# didah.net
KiCad netlist of a schematic drawn in EAGLE
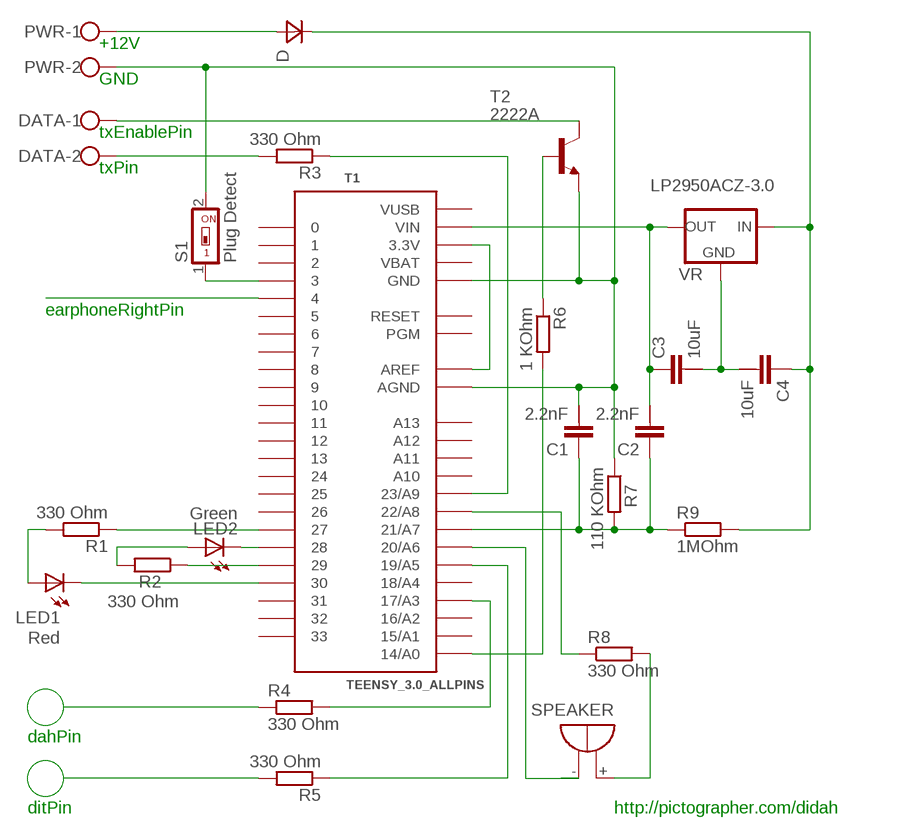
[diagram p0: schematic, sheet 1]

(export (version "E")
  (design (tool "Eeschema 10.0.6"))
  (components
    (comp (ref "C1")
      (value "2.2nF")
      (footprint "eagle-import:C2.5_5-6")
      (libsource (lib "eagle-import") (part "C-2.5-5/6"))
    )
    (comp (ref "C2")
      (value "2.2nF")
      (footprint "eagle-import:C2.5_5-6")
      (libsource (lib "eagle-import") (part "C-2.5-5/6"))
    )
    (comp (ref "C3")
      (value "10uF")
      (footprint "eagle-import:C2.5_5-6")
      (libsource (lib "eagle-import") (part "C-2.5-5/6"))
    )
    (comp (ref "C4")
      (value "10uF")
      (footprint "eagle-import:C2.5_5-6")
      (libsource (lib "eagle-import") (part "C-2.5-5/6"))
    )
    (comp (ref "D")
      (value "DIODE")
      (footprint "eagle-import:DIODE")
      (libsource (lib "eagle-import") (part "DIODE"))
    )
    (comp (ref "DATA")
      (value "W237-102")
      (footprint "eagle-import:W237-102")
      (fields (field (name "MPN") "237-102"))
      (libsource (lib "eagle-import") (part "W237-102"))
    )
    (comp (ref "LED1")
      (value "Red")
      (footprint "eagle-import:LED_SML0603")
      (libsource (lib "eagle-import") (part "LED_ESML0603"))
    )
    (comp (ref "LED2")
      (value "Green")
      (footprint "eagle-import:LED_SML0603")
      (libsource (lib "eagle-import") (part "LED_ESML0603"))
    )
    (comp (ref "PWR")
      (value "W237-102")
      (footprint "eagle-import:W237-102")
      (fields (field (name "MPN") "237-102"))
      (libsource (lib "eagle-import") (part "W237-102"))
    )
    (comp (ref "R1")
      (value "330 Ohm")
      (footprint "eagle-import:R0402")
      (libsource (lib "eagle-import") (part "RR0402"))
    )
    (comp (ref "R2")
      (value "330 Ohm")
      (footprint "eagle-import:R0402")
      (libsource (lib "eagle-import") (part "RR0402"))
    )
    (comp (ref "R3")
      (value "330 Ohm")
      (footprint "eagle-import:R0402")
      (libsource (lib "eagle-import") (part "RR0402"))
    )
    (comp (ref "R4")
      (value "330 Ohm")
      (footprint "eagle-import:R0402")
      (libsource (lib "eagle-import") (part "RR0402"))
    )
    (comp (ref "R5")
      (value "330 Ohm")
      (footprint "eagle-import:R0402")
      (libsource (lib "eagle-import") (part "RR0402"))
    )
    (comp (ref "R6")
      (value "1 KOhm")
      (footprint "eagle-import:R0402")
      (libsource (lib "eagle-import") (part "RR0402"))
    )
    (comp (ref "R7")
      (value "110 KOhm")
      (footprint "eagle-import:0204_7")
      (libsource (lib "eagle-import") (part "R0204/7"))
    )
    (comp (ref "R8")
      (value "330 Ohm")
      (footprint "eagle-import:R0402")
      (libsource (lib "eagle-import") (part "RR0402"))
    )
    (comp (ref "R9")
      (value "1MOhm")
      (footprint "eagle-import:0204_7")
      (libsource (lib "eagle-import") (part "R0204/7"))
    )
    (comp (ref "S1")
      (value "Plug Detect")
      (footprint "eagle-import:SMS-001")
      (libsource (lib "eagle-import") (part "SWS001"))
    )
    (comp (ref "SPEAKER")
      (value "BMT1205XH7.5")
      (footprint "eagle-import:BMT1205XH7.5")
      (libsource (lib "eagle-import") (part "BMT1205XH7.5"))
    )
    (comp (ref "T1")
      (value "TEENSY_3.0_ALLPINS")
      (footprint "eagle-import:TEENSY_3.0_ALLPINS")
      (libsource (lib "eagle-import") (part "TEENSY_3.0_ALLPINS"))
    )
    (comp (ref "T2")
      (value "2222A")
      (footprint "eagle-import:TO92-EBC")
      (libsource (lib "eagle-import") (part "-NPN-TO92-EBC2N2222"))
    )
    (comp (ref "VR")
      (value "LP2950ACZ-3.0")
      (footprint "eagle-import:TO92")
      (libsource (lib "eagle-import") (part "LP2950?ACZ-3.0"))
    )
  )
  (nets
    (net (code "1") (name "/VBAT") (class "Default")
      (node (ref "T1") (pin "VBAT") (pinfunction "VBAT_VBAT") (pintype "power_in"))
    )
    (net (code "2") (name "/VUSB") (class "Default")
      (node (ref "T1") (pin "VUSB") (pinfunction "VUSB_VUSB") (pintype "power_in"))
    )
    (net (code "3") (name "Net-(C1-Pad1)") (class "Default")
      (node (ref "C1") (pin "1") (pinfunction "1_1") (pintype "passive"))
      (node (ref "C2") (pin "1") (pinfunction "1_1") (pintype "passive"))
      (node (ref "R7") (pin "2") (pinfunction "2_2") (pintype "passive"))
      (node (ref "R9") (pin "1") (pinfunction "1_1") (pintype "passive"))
      (node (ref "T1") (pin "21/A7") (pinfunction "21/A7_21/A7") (pintype "bidirectional"))
    )
    (net (code "4") (name "Net-(DATAA-KL)") (class "Default")
      (node (ref "DATA") (pin "1") (pinfunction "KL_1") (pintype "passive"))
      (node (ref "T2") (pin "C") (pinfunction "C_C") (pintype "passive"))
    )
    (net (code "5") (name "Net-(DATAB-KL)") (class "Default")
      (node (ref "DATA") (pin "2") (pinfunction "KL_2") (pintype "passive"))
      (node (ref "R3") (pin "2") (pinfunction "2_2") (pintype "passive"))
    )
    (net (code "6") (name "Net-(LED1-PadA)") (class "Default")
      (node (ref "LED1") (pin "A") (pinfunction "A_A") (pintype "passive"))
      (node (ref "R1") (pin "2") (pinfunction "2_2") (pintype "passive"))
    )
    (net (code "7") (name "Net-(LED1-PadC)") (class "Default")
      (node (ref "LED1") (pin "C") (pinfunction "C_C") (pintype "passive"))
      (node (ref "T1") (pin "30") (pinfunction "30_30") (pintype "bidirectional"))
    )
    (net (code "8") (name "Net-(LED2-PadA)") (class "Default")
      (node (ref "LED2") (pin "A") (pinfunction "A_A") (pintype "passive"))
      (node (ref "R2") (pin "2") (pinfunction "2_2") (pintype "passive"))
    )
    (net (code "9") (name "Net-(LED2-PadC)") (class "Default")
      (node (ref "LED2") (pin "C") (pinfunction "C_C") (pintype "passive"))
      (node (ref "T1") (pin "28") (pinfunction "28_28") (pintype "bidirectional"))
    )
    (net (code "10") (name "Net-(PWRA-KL)") (class "Default")
      (node (ref "D") (pin "C") (pinfunction "C_C") (pintype "input"))
      (node (ref "PWR") (pin "1") (pinfunction "KL_1") (pintype "passive"))
    )
    (net (code "11") (name "Net-(PWRB-KL)") (class "Default")
      (node (ref "C1") (pin "2") (pinfunction "2_2") (pintype "passive"))
      (node (ref "PWR") (pin "2") (pinfunction "KL_2") (pintype "passive"))
      (node (ref "R7") (pin "1") (pinfunction "1_1") (pintype "passive"))
      (node (ref "S1") (pin "2") (pinfunction "2_2") (pintype "passive"))
      (node (ref "T1") (pin "AGND") (pinfunction "AGND_AGND") (pintype "power_in"))
      (node (ref "T1") (pin "GND") (pinfunction "GND_GND") (pintype "power_in"))
      (node (ref "T1") (pin "GND1") (pinfunction "GND_GND1") (pintype "power_in"))
      (node (ref "T1") (pin "GND2") (pinfunction "GND_GND2") (pintype "power_in"))
      (node (ref "T2") (pin "E") (pinfunction "E_E") (pintype "passive"))
    )
    (net (code "12") (name "Net-(R1-Pad1)") (class "Default")
      (node (ref "R1") (pin "1") (pinfunction "1_1") (pintype "passive"))
      (node (ref "T1") (pin "27") (pinfunction "27_27") (pintype "bidirectional"))
    )
    (net (code "13") (name "Net-(R2-Pad1)") (class "Default")
      (node (ref "R2") (pin "1") (pinfunction "1_1") (pintype "passive"))
      (node (ref "T1") (pin "29") (pinfunction "29_29") (pintype "bidirectional"))
    )
    (net (code "14") (name "Net-(R3-Pad1)") (class "Default")
      (node (ref "R3") (pin "1") (pinfunction "1_1") (pintype "passive"))
      (node (ref "T1") (pin "23/A9") (pinfunction "23/A9_23/A9") (pintype "bidirectional"))
    )
    (net (code "15") (name "Net-(R4-Pad2)") (class "Default")
      (node (ref "R4") (pin "2") (pinfunction "2_2") (pintype "passive"))
      (node (ref "T1") (pin "17/A3") (pinfunction "17/A3_17/A3") (pintype "bidirectional"))
    )
    (net (code "16") (name "Net-(R5-Pad1)") (class "Default")
      (node (ref "R5") (pin "1") (pinfunction "1_1") (pintype "passive"))
      (node (ref "T1") (pin "19/A5") (pinfunction "19/A5_19/A5") (pintype "bidirectional"))
    )
    (net (code "17") (name "Net-(R6-Pad1)") (class "Default")
      (node (ref "R6") (pin "1") (pinfunction "1_1") (pintype "passive"))
      (node (ref "T2") (pin "B") (pinfunction "B_B") (pintype "passive"))
    )
    (net (code "18") (name "Net-(R6-Pad2)") (class "Default")
      (node (ref "R6") (pin "2") (pinfunction "2_2") (pintype "passive"))
      (node (ref "T1") (pin "14/A0") (pinfunction "14/A0_14/A0") (pintype "bidirectional"))
    )
    (net (code "19") (name "Net-(R8-Pad1)") (class "Default")
      (node (ref "R8") (pin "1") (pinfunction "1_1") (pintype "passive"))
      (node (ref "T1") (pin "22/A8") (pinfunction "22/A8_22/A8") (pintype "bidirectional"))
    )
    (net (code "20") (name "Net-(R8-Pad2)") (class "Default")
      (node (ref "R8") (pin "2") (pinfunction "2_2") (pintype "passive"))
      (node (ref "SPEAKER") (pin "+") (pinfunction "+_+") (pintype "passive"))
    )
    (net (code "21") (name "Net-(S1-Pad1)") (class "Default")
      (node (ref "S1") (pin "1") (pinfunction "1_1") (pintype "passive"))
      (node (ref "T1") (pin "3") (pinfunction "3_3") (pintype "bidirectional"))
    )
    (net (code "22") (name "Net-(SPEAKER-Pad-)") (class "Default")
      (node (ref "SPEAKER") (pin "-") (pinfunction "-_-") (pintype "passive"))
      (node (ref "T1") (pin "20/A6") (pinfunction "20/A6_20/A6") (pintype "bidirectional"))
    )
    (net (code "23") (name "Net-(T1-3.3V-Pad3.3V1)") (class "Default")
      (node (ref "T1") (pin "3.3V") (pinfunction "3.3V_3.3V") (pintype "power_in"))
      (node (ref "T1") (pin "3.3V1") (pinfunction "3.3V_3.3V1") (pintype "power_in"))
      (node (ref "T1") (pin "3.3V2") (pinfunction "3.3V_3.3V2") (pintype "power_in"))
      (node (ref "T1") (pin "AREF") (pinfunction "AREF_AREF") (pintype "power_in"))
    )
    (net (code "24") (name "Net-(VR-GND)") (class "Default")
      (node (ref "C3") (pin "2") (pinfunction "2_2") (pintype "passive"))
      (node (ref "C4") (pin "2") (pinfunction "2_2") (pintype "passive"))
      (node (ref "VR") (pin "2") (pinfunction "GND_2") (pintype "input"))
    )
    (net (code "25") (name "Net-(VR-IN)") (class "Default")
      (node (ref "C4") (pin "1") (pinfunction "1_1") (pintype "passive"))
      (node (ref "D") (pin "A") (pinfunction "A_A") (pintype "input"))
      (node (ref "R9") (pin "2") (pinfunction "2_2") (pintype "passive"))
      (node (ref "VR") (pin "3") (pinfunction "IN_3") (pintype "input"))
    )
    (net (code "26") (name "Net-(VR-OUT)") (class "Default")
      (node (ref "C2") (pin "2") (pinfunction "2_2") (pintype "passive"))
      (node (ref "C3") (pin "1") (pinfunction "1_1") (pintype "passive"))
      (node (ref "T1") (pin "VIN") (pinfunction "VIN_VIN") (pintype "power_in"))
      (node (ref "VR") (pin "1") (pinfunction "OUT_1") (pintype "passive"))
    )
    (net (code "27") (name "unconnected-(C1-Pad3)") (class "Default")
      (node (ref "C1") (pin "3") (pinfunction "3_3") (pintype "passive"))
    )
    (net (code "28") (name "unconnected-(C2-Pad3)") (class "Default")
      (node (ref "C2") (pin "3") (pinfunction "3_3") (pintype "passive"))
    )
    (net (code "29") (name "unconnected-(C3-Pad3)") (class "Default")
      (node (ref "C3") (pin "3") (pinfunction "3_3") (pintype "passive"))
    )
    (net (code "30") (name "unconnected-(C4-Pad3)") (class "Default")
      (node (ref "C4") (pin "3") (pinfunction "3_3") (pintype "passive"))
    )
    (net (code "31") (name "unconnected-(R4-Pad1)") (class "Default")
      (node (ref "R4") (pin "1") (pinfunction "1_1") (pintype "passive"))
    )
    (net (code "32") (name "unconnected-(R5-Pad2)") (class "Default")
      (node (ref "R5") (pin "2") (pinfunction "2_2") (pintype "passive"))
    )
    (net (code "33") (name "unconnected-(T1-Pad0)") (class "Default")
      (node (ref "T1") (pin "0") (pinfunction "0_0") (pintype "bidirectional"))
    )
    (net (code "34") (name "unconnected-(T1-Pad1)") (class "Default")
      (node (ref "T1") (pin "1") (pinfunction "1_1") (pintype "bidirectional"))
    )
    (net (code "35") (name "unconnected-(T1-Pad2)") (class "Default")
      (node (ref "T1") (pin "2") (pinfunction "2_2") (pintype "bidirectional"))
    )
    (net (code "36") (name "unconnected-(T1-Pad4)") (class "Default")
      (node (ref "T1") (pin "4") (pinfunction "4_4") (pintype "bidirectional"))
    )
    (net (code "37") (name "unconnected-(T1-Pad5)") (class "Default")
      (node (ref "T1") (pin "5") (pinfunction "5_5") (pintype "bidirectional"))
    )
    (net (code "38") (name "unconnected-(T1-Pad6)") (class "Default")
      (node (ref "T1") (pin "6") (pinfunction "6_6") (pintype "bidirectional"))
    )
    (net (code "39") (name "unconnected-(T1-Pad7)") (class "Default")
      (node (ref "T1") (pin "7") (pinfunction "7_7") (pintype "bidirectional"))
    )
    (net (code "40") (name "unconnected-(T1-Pad8)") (class "Default")
      (node (ref "T1") (pin "8") (pinfunction "8_8") (pintype "bidirectional"))
    )
    (net (code "41") (name "unconnected-(T1-Pad9)") (class "Default")
      (node (ref "T1") (pin "9") (pinfunction "9_9") (pintype "bidirectional"))
    )
    (net (code "42") (name "unconnected-(T1-Pad10)") (class "Default")
      (node (ref "T1") (pin "10") (pinfunction "10_10") (pintype "bidirectional"))
    )
    (net (code "43") (name "unconnected-(T1-Pad11)") (class "Default")
      (node (ref "T1") (pin "11") (pinfunction "11_11") (pintype "bidirectional"))
    )
    (net (code "44") (name "unconnected-(T1-Pad12)") (class "Default")
      (node (ref "T1") (pin "12") (pinfunction "12_12") (pintype "bidirectional"))
    )
    (net (code "45") (name "unconnected-(T1-Pad13)") (class "Default")
      (node (ref "T1") (pin "13") (pinfunction "13_13") (pintype "bidirectional"))
    )
    (net (code "46") (name "unconnected-(T1-Pad15{slash}A1)") (class "Default")
      (node (ref "T1") (pin "15/A1") (pinfunction "15/A1_15/A1") (pintype "bidirectional"))
    )
    (net (code "47") (name "unconnected-(T1-Pad16{slash}A2)") (class "Default")
      (node (ref "T1") (pin "16/A2") (pinfunction "16/A2_16/A2") (pintype "bidirectional"))
    )
    (net (code "48") (name "unconnected-(T1-Pad18{slash}A4)") (class "Default")
      (node (ref "T1") (pin "18/A4") (pinfunction "18/A4_18/A4") (pintype "bidirectional"))
    )
    (net (code "49") (name "unconnected-(T1-Pad24)") (class "Default")
      (node (ref "T1") (pin "24") (pinfunction "24_24") (pintype "bidirectional"))
    )
    (net (code "50") (name "unconnected-(T1-Pad25)") (class "Default")
      (node (ref "T1") (pin "25") (pinfunction "25_25") (pintype "bidirectional"))
    )
    (net (code "51") (name "unconnected-(T1-Pad26)") (class "Default")
      (node (ref "T1") (pin "26") (pinfunction "26_26") (pintype "bidirectional"))
    )
    (net (code "52") (name "unconnected-(T1-Pad31)") (class "Default")
      (node (ref "T1") (pin "31") (pinfunction "31_31") (pintype "bidirectional"))
    )
    (net (code "53") (name "unconnected-(T1-Pad32)") (class "Default")
      (node (ref "T1") (pin "32") (pinfunction "32_32") (pintype "bidirectional"))
    )
    (net (code "54") (name "unconnected-(T1-Pad33)") (class "Default")
      (node (ref "T1") (pin "33") (pinfunction "33_33") (pintype "bidirectional"))
    )
    (net (code "55") (name "unconnected-(T1-PadA10)") (class "Default")
      (node (ref "T1") (pin "A10") (pinfunction "A10_A10") (pintype "bidirectional"))
    )
    (net (code "56") (name "unconnected-(T1-PadA11)") (class "Default")
      (node (ref "T1") (pin "A11") (pinfunction "A11_A11") (pintype "bidirectional"))
    )
    (net (code "57") (name "unconnected-(T1-PadA12)") (class "Default")
      (node (ref "T1") (pin "A12") (pinfunction "A12_A12") (pintype "bidirectional"))
    )
    (net (code "58") (name "unconnected-(T1-PadA13)") (class "Default")
      (node (ref "T1") (pin "A13") (pinfunction "A13_A13") (pintype "bidirectional"))
    )
    (net (code "59") (name "unconnected-(T1-PadPGM)") (class "Default")
      (node (ref "T1") (pin "PGM") (pinfunction "PGM_PGM") (pintype "bidirectional"))
    )
    (net (code "60") (name "unconnected-(T1-PadRESET)") (class "Default")
      (node (ref "T1") (pin "RESET") (pinfunction "RESET_RESET") (pintype "bidirectional"))
    )
  )
)
